# sinket.net
KiCad netlist of a schematic drawn in EAGLE
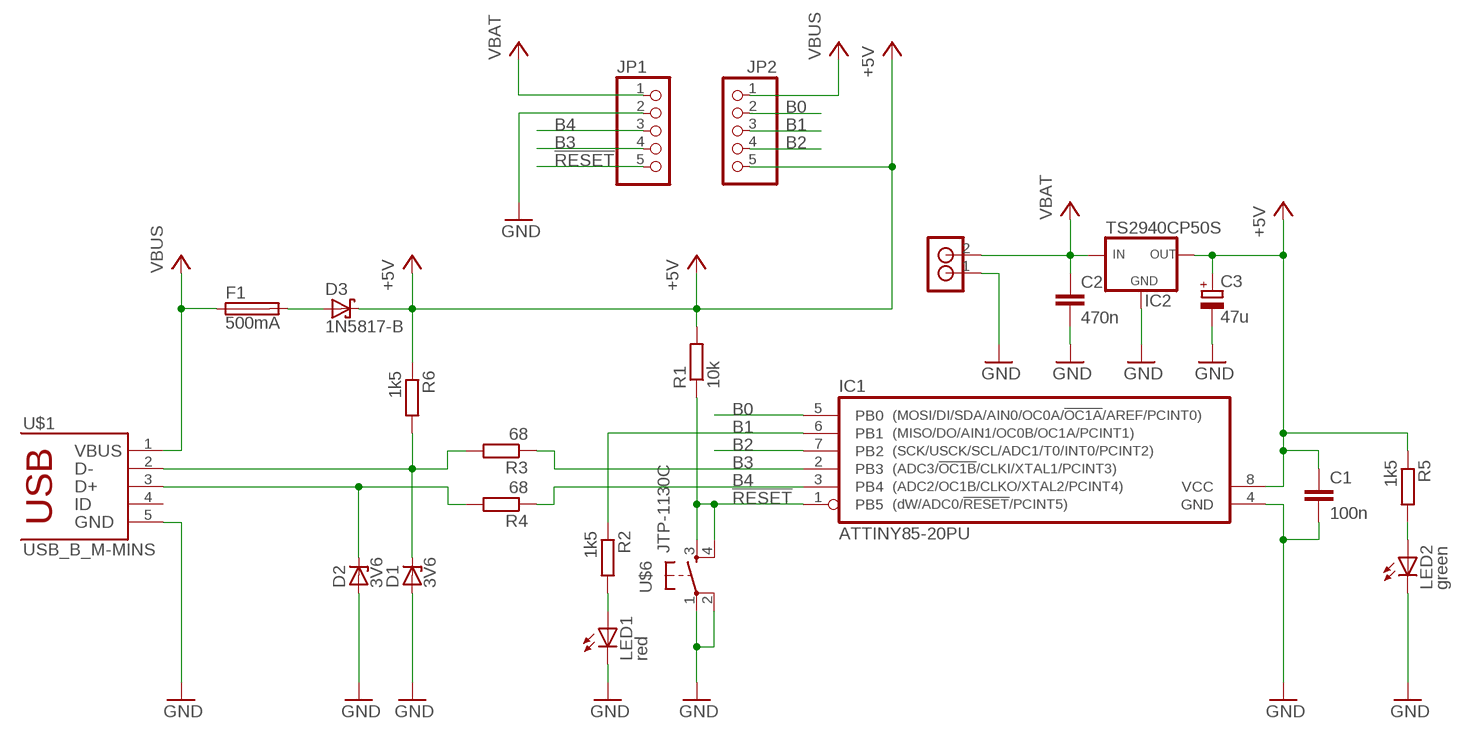
[diagram p0: schematic, sheet 1]

(export (version "E")
  (design (tool "Eeschema 10.0.6"))
  (components
    (comp (ref "C1")
      (value "100n")
      (footprint "eagle-import:C1206")
      (libsource (lib "eagle-import") (part "C-EUC1206"))
    )
    (comp (ref "C2")
      (value "470n")
      (footprint "eagle-import:C050-025X075")
      (libsource (lib "eagle-import") (part "C-EU050-025X075"))
    )
    (comp (ref "C3")
      (value "47u")
      (footprint "eagle-import:E2,5-6")
      (libsource (lib "eagle-import") (part "CPOL-EUE2.5-6"))
    )
    (comp (ref "D1")
      (value "3V6")
      (footprint "eagle-import:SOD80C")
      (libsource (lib "eagle-import") (part "ZENER-DIODESOD80C"))
    )
    (comp (ref "D2")
      (value "3V6")
      (footprint "eagle-import:SOD80C")
      (libsource (lib "eagle-import") (part "ZENER-DIODESOD80C"))
    )
    (comp (ref "D3")
      (value "1N5817-B")
      (footprint "eagle-import:DO41-7.6")
      (libsource (lib "eagle-import") (part "1N5817-B"))
    )
    (comp (ref "F1")
      (value "500mA")
      (footprint "eagle-import:LP60-050")
      (libsource (lib "eagle-import") (part "PTC-FUSE-LP60-050"))
    )
    (comp (ref "IC1")
      (value "ATTINY85-20PU")
      (footprint "eagle-import:8P3")
      (libsource (lib "eagle-import") (part "ATTINY25PU-20"))
    )
    (comp (ref "IC2")
      (value "TS2940CP50S")
      (footprint "eagle-import:TO-252")
      (libsource (lib "eagle-import") (part "TS2940SCP50"))
    )
    (comp (ref "JP1")
      (value "PINHD-1X5")
      (footprint "eagle-import:1X05")
      (libsource (lib "eagle-import") (part "PINHD-1X5"))
    )
    (comp (ref "JP2")
      (value "PINHD-1X5")
      (footprint "eagle-import:1X05")
      (libsource (lib "eagle-import") (part "PINHD-1X5"))
    )
    (comp (ref "LED1")
      (value "red")
      (footprint "eagle-import:LED5MM")
      (libsource (lib "eagle-import") (part "LED5MM"))
    )
    (comp (ref "LED2")
      (value "green")
      (footprint "eagle-import:LED5MM")
      (libsource (lib "eagle-import") (part "LED5MM"))
    )
    (comp (ref "R1")
      (value "10k")
      (footprint "eagle-import:R1206")
      (libsource (lib "eagle-import") (part "R-EU_R1206"))
    )
    (comp (ref "R2")
      (value "1k5")
      (footprint "eagle-import:R1206")
      (libsource (lib "eagle-import") (part "R-EU_R1206"))
    )
    (comp (ref "R3")
      (value "68")
      (footprint "eagle-import:R1206")
      (libsource (lib "eagle-import") (part "R-EU_R1206"))
    )
    (comp (ref "R4")
      (value "68")
      (footprint "eagle-import:R1206")
      (libsource (lib "eagle-import") (part "R-EU_R1206"))
    )
    (comp (ref "R5")
      (value "1k5")
      (footprint "eagle-import:R1206")
      (libsource (lib "eagle-import") (part "R-EU_R1206"))
    )
    (comp (ref "R6")
      (value "1k5")
      (footprint "eagle-import:R1206")
      (libsource (lib "eagle-import") (part "R-EU_R1206"))
    )
    (comp (ref "U$1")
      (value "USB_B_M-MINS")
      (footprint "eagle-import:LUMBERG_2486-01")
      (libsource (lib "eagle-import") (part "USB_B_M-MINS"))
    )
    (comp (ref "U$6")
      (value "JTP-1130C")
      (footprint "eagle-import:JTP-1130")
      (libsource (lib "eagle-import") (part "JTP-1130C"))
    )
    (comp (ref "U$7")
      (value "RIACON_101_2")
      (footprint "eagle-import:RIACON_101_2")
      (libsource (lib "eagle-import") (part "RIACON_101_2"))
    )
  )
  (nets
    (net (code "1") (name "+5V") (class "Default")
      (node (ref "C1") (pin "1") (pinfunction "1_1") (pintype "passive"))
      (node (ref "C3") (pin "+") (pinfunction "+_+") (pintype "passive"))
      (node (ref "D3") (pin "C") (pinfunction "C_C") (pintype "passive"))
      (node (ref "IC1") (pin "8") (pinfunction "VCC_8") (pintype "power_in"))
      (node (ref "IC2") (pin "3") (pinfunction "OUT_3") (pintype "power_in"))
      (node (ref "JP2") (pin "5") (pinfunction "5_5") (pintype "passive"))
      (node (ref "R1") (pin "2") (pinfunction "2_2") (pintype "passive"))
      (node (ref "R5") (pin "1") (pinfunction "1_1") (pintype "passive"))
      (node (ref "R6") (pin "1") (pinfunction "1_1") (pintype "passive"))
    )
    (net (code "2") (name "/B0") (class "Default")
      (node (ref "IC1") (pin "5") (pinfunction "PB0_5") (pintype "bidirectional"))
      (node (ref "JP2") (pin "2") (pinfunction "2_2") (pintype "passive"))
    )
    (net (code "3") (name "/B1") (class "Default")
      (node (ref "IC1") (pin "6") (pinfunction "PB1_6") (pintype "bidirectional"))
      (node (ref "JP2") (pin "3") (pinfunction "3_3") (pintype "passive"))
      (node (ref "R2") (pin "1") (pinfunction "1_1") (pintype "passive"))
    )
    (net (code "4") (name "/B2") (class "Default")
      (node (ref "IC1") (pin "7") (pinfunction "PB2_7") (pintype "bidirectional"))
      (node (ref "JP2") (pin "4") (pinfunction "4_4") (pintype "passive"))
    )
    (net (code "5") (name "/B3") (class "Default")
      (node (ref "IC1") (pin "2") (pinfunction "PB3_2") (pintype "bidirectional"))
      (node (ref "JP1") (pin "4") (pinfunction "4_4") (pintype "passive"))
      (node (ref "R3") (pin "1") (pinfunction "1_1") (pintype "passive"))
    )
    (net (code "6") (name "/B4") (class "Default")
      (node (ref "IC1") (pin "3") (pinfunction "PB4_3") (pintype "bidirectional"))
      (node (ref "JP1") (pin "3") (pinfunction "3_3") (pintype "passive"))
      (node (ref "R4") (pin "1") (pinfunction "1_1") (pintype "passive"))
    )
    (net (code "7") (name "/~{RESET}") (class "Default")
      (node (ref "IC1") (pin "1") (pinfunction "PB5_1") (pintype "bidirectional"))
      (node (ref "JP1") (pin "5") (pinfunction "5_5") (pintype "passive"))
      (node (ref "R1") (pin "1") (pinfunction "1_1") (pintype "passive"))
      (node (ref "U$6") (pin "3") (pinfunction "S_3") (pintype "passive"))
      (node (ref "U$6") (pin "4") (pinfunction "S1_4") (pintype "passive"))
    )
    (net (code "8") (name "GND") (class "Default")
      (node (ref "C1") (pin "2") (pinfunction "2_2") (pintype "passive"))
      (node (ref "C2") (pin "2") (pinfunction "2_2") (pintype "passive"))
      (node (ref "C3") (pin "-") (pinfunction "-_-") (pintype "passive"))
      (node (ref "D1") (pin "A") (pinfunction "A_A") (pintype "passive"))
      (node (ref "D2") (pin "A") (pinfunction "A_A") (pintype "passive"))
      (node (ref "IC1") (pin "4") (pinfunction "GND_4") (pintype "power_in"))
      (node (ref "IC2") (pin "2") (pinfunction "GND_2") (pintype "power_in"))
      (node (ref "JP1") (pin "2") (pinfunction "2_2") (pintype "passive"))
      (node (ref "LED1") (pin "K") (pinfunction "C_K") (pintype "passive"))
      (node (ref "LED2") (pin "K") (pinfunction "C_K") (pintype "passive"))
      (node (ref "U$1") (pin "5") (pinfunction "5_5") (pintype "passive"))
      (node (ref "U$6") (pin "1") (pinfunction "P_1") (pintype "passive"))
      (node (ref "U$6") (pin "2") (pinfunction "P1_2") (pintype "passive"))
      (node (ref "U$7") (pin "1") (pinfunction "1_1") (pintype "passive"))
    )
    (net (code "9") (name "Net-(D1-PadC)") (class "Default")
      (node (ref "D1") (pin "C") (pinfunction "C_C") (pintype "passive"))
      (node (ref "R3") (pin "2") (pinfunction "2_2") (pintype "passive"))
      (node (ref "R6") (pin "2") (pinfunction "2_2") (pintype "passive"))
      (node (ref "U$1") (pin "2") (pinfunction "2_2") (pintype "passive"))
    )
    (net (code "10") (name "Net-(D2-PadC)") (class "Default")
      (node (ref "D2") (pin "C") (pinfunction "C_C") (pintype "passive"))
      (node (ref "R4") (pin "2") (pinfunction "2_2") (pintype "passive"))
      (node (ref "U$1") (pin "3") (pinfunction "3_3") (pintype "passive"))
    )
    (net (code "11") (name "Net-(F1-2)") (class "Default")
      (node (ref "D3") (pin "A") (pinfunction "A_A") (pintype "passive"))
      (node (ref "F1") (pin "P$2") (pinfunction "2_P$2") (pintype "passive"))
    )
    (net (code "12") (name "Net-(LED1-PadA)") (class "Default")
      (node (ref "LED1") (pin "A") (pinfunction "A_A") (pintype "passive"))
      (node (ref "R2") (pin "2") (pinfunction "2_2") (pintype "passive"))
    )
    (net (code "13") (name "Net-(LED2-PadA)") (class "Default")
      (node (ref "LED2") (pin "A") (pinfunction "A_A") (pintype "passive"))
      (node (ref "R5") (pin "2") (pinfunction "2_2") (pintype "passive"))
    )
    (net (code "14") (name "VBAT") (class "Default")
      (node (ref "C2") (pin "1") (pinfunction "1_1") (pintype "passive"))
      (node (ref "IC2") (pin "1") (pinfunction "IN_1") (pintype "power_in"))
      (node (ref "JP1") (pin "1") (pinfunction "1_1") (pintype "passive"))
      (node (ref "U$7") (pin "2") (pinfunction "2_2") (pintype "passive"))
    )
    (net (code "15") (name "VBUS") (class "Default")
      (node (ref "F1") (pin "P$1") (pinfunction "1_P$1") (pintype "passive"))
      (node (ref "JP2") (pin "1") (pinfunction "1_1") (pintype "passive"))
      (node (ref "U$1") (pin "1") (pinfunction "1_1") (pintype "passive"))
    )
    (net (code "16") (name "unconnected-(U$1-Pad4)") (class "Default")
      (node (ref "U$1") (pin "4") (pinfunction "4_4") (pintype "passive"))
    )
  )
)
